# 04_InterfacePart.net
KiCad netlist of a schematic drawn in EasyEDA Pro
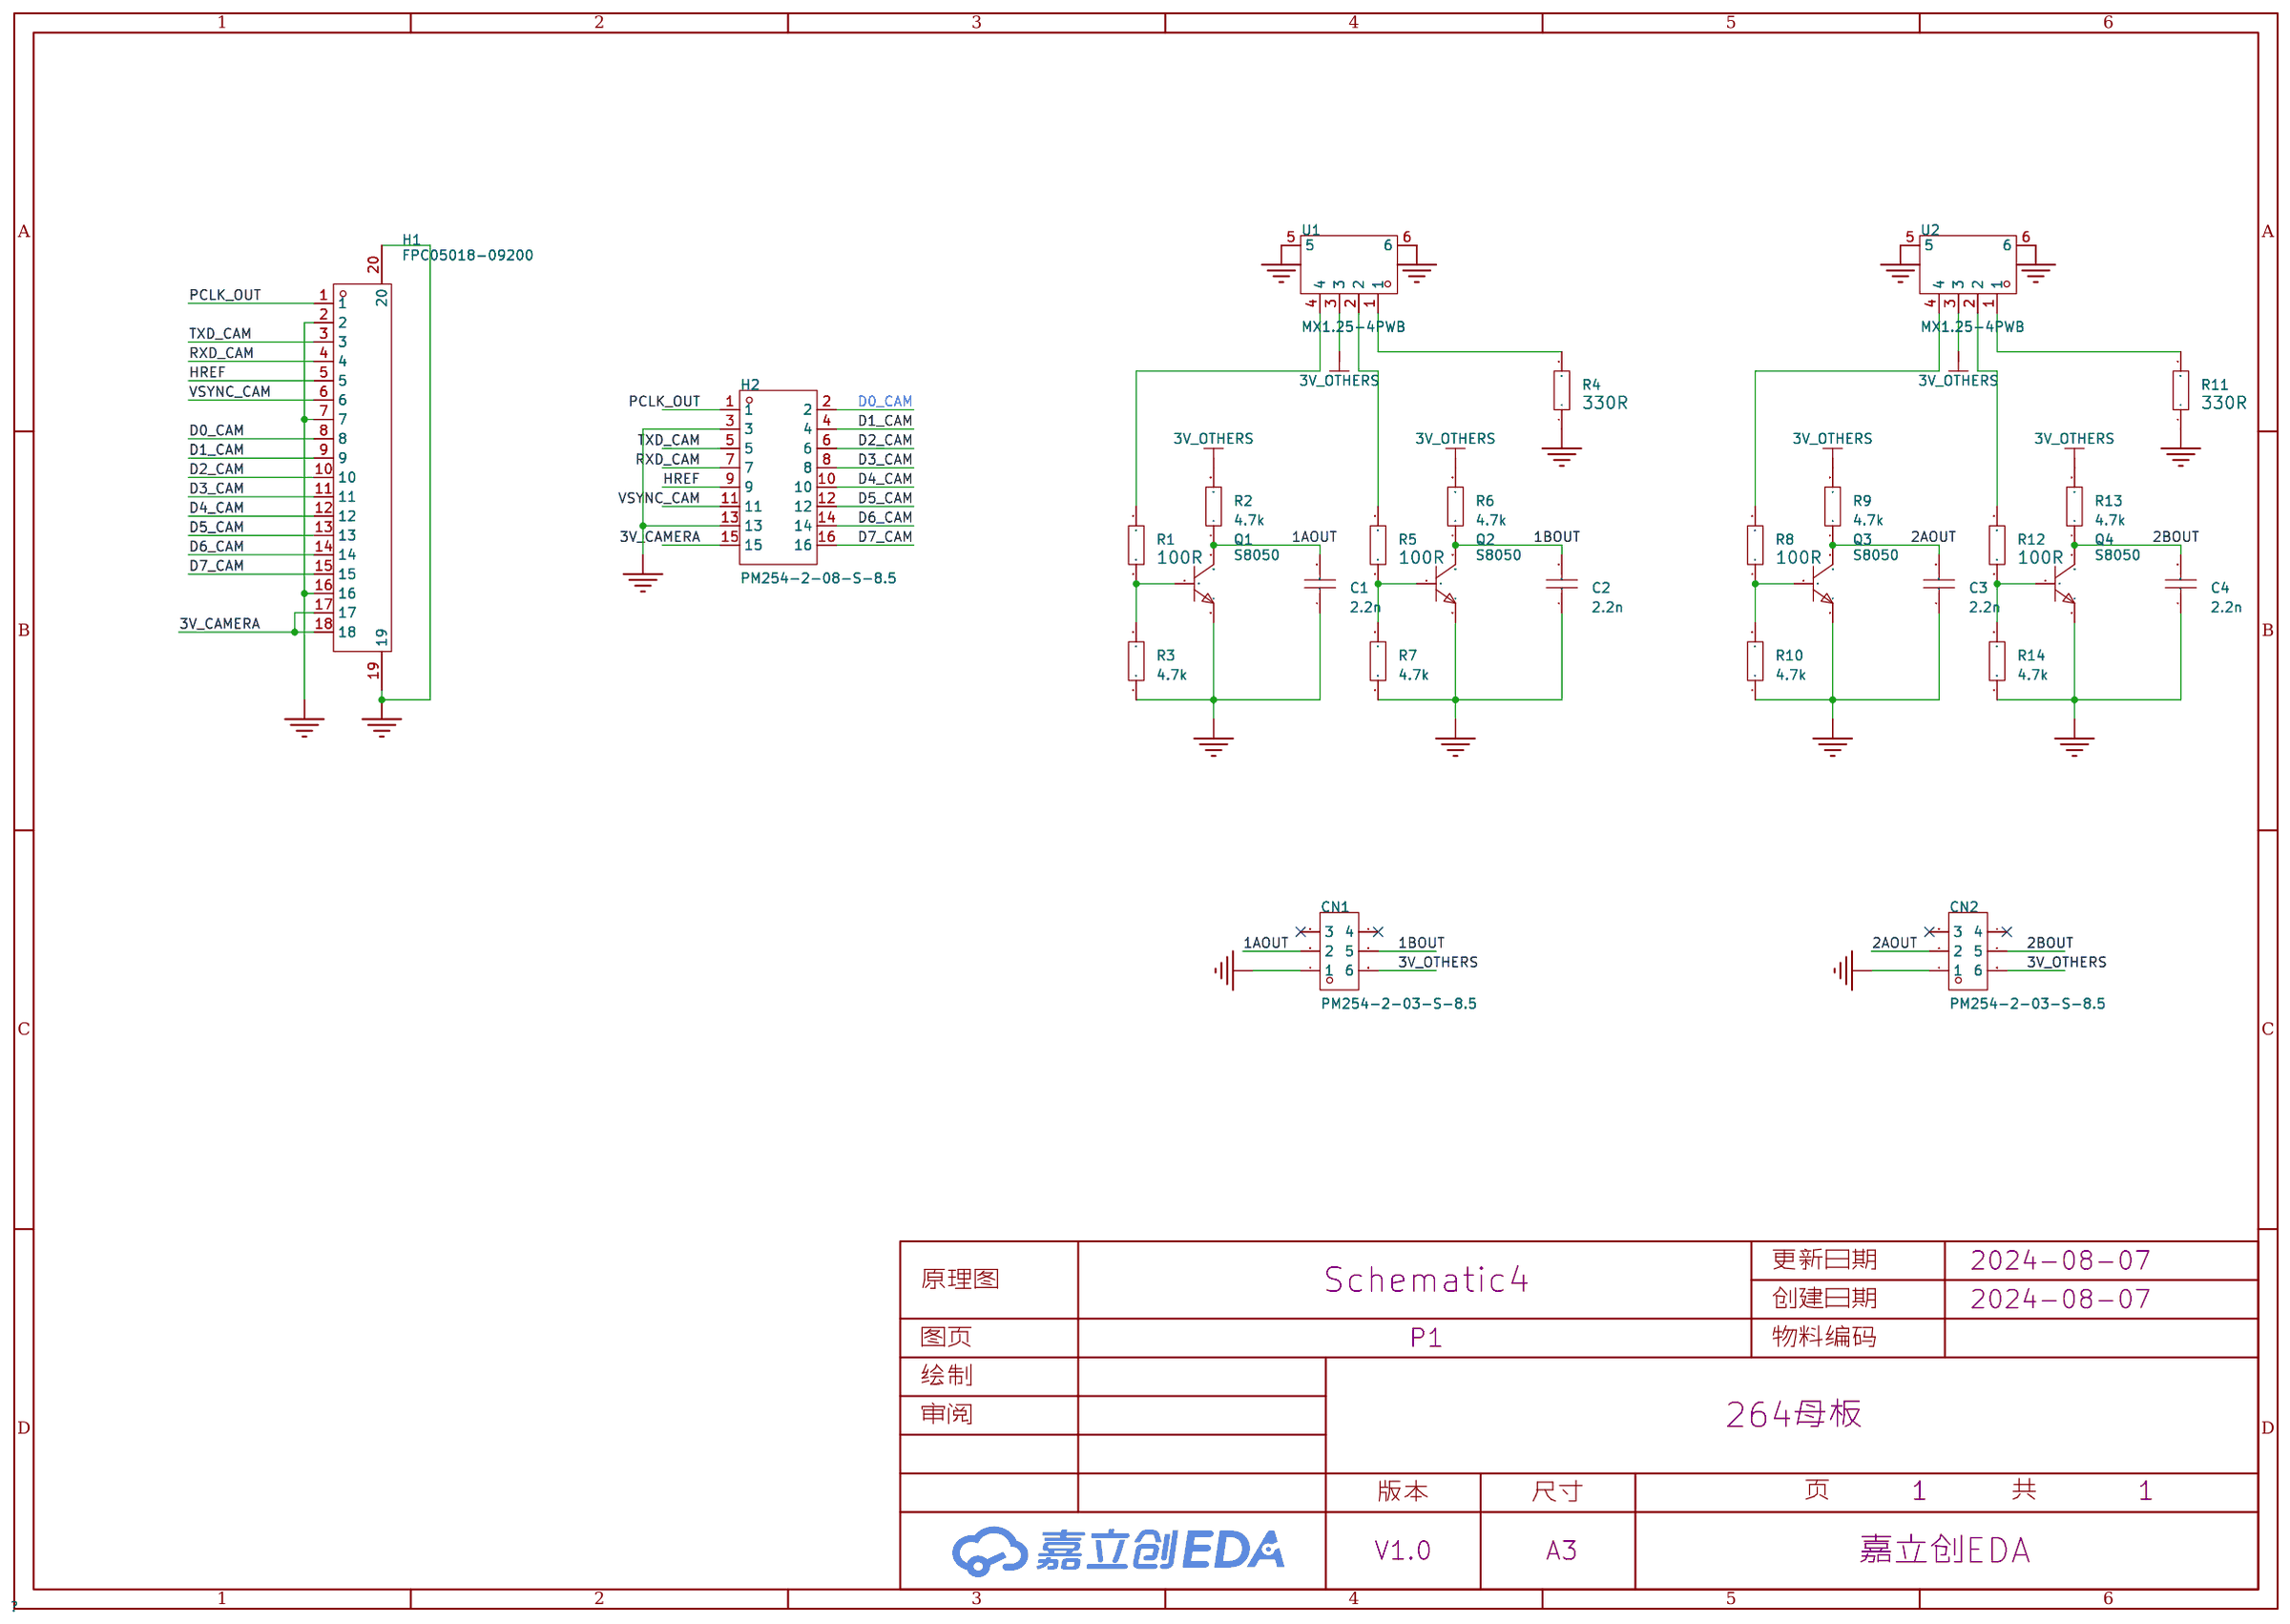
[diagram p0: schematic sheet]

(export (version "E")
  (design (tool "Eeschema 10.0.6"))
  (components
    (comp (ref "C1")
      (value "2.2n")
      (footprint "easyedapro:C0805")
      (libsource (lib "easyedapro") (part "电容-0805C"))
    )
    (comp (ref "C2")
      (value "2.2n")
      (footprint "easyedapro:C0805")
      (libsource (lib "easyedapro") (part "电容-0805C"))
    )
    (comp (ref "C3")
      (value "2.2n")
      (footprint "easyedapro:C0805")
      (libsource (lib "easyedapro") (part "电容-0805C"))
    )
    (comp (ref "C4")
      (value "2.2n")
      (footprint "easyedapro:C0805")
      (libsource (lib "easyedapro") (part "电容-0805C"))
    )
    (comp (ref "CN1")
      (value "PM254-2-03-S-8.5")
      (footprint "easyedapro:HDR-SMD_6P-P2.54-V-F-R2-C3-LS7.0")
      (fields (field (name "Manufacturer") "HCTL(华灿天禄)"))
      (libsource (lib "easyedapro") (part "PM254-2-03-S-8.5"))
    )
    (comp (ref "CN2")
      (value "PM254-2-03-S-8.5")
      (footprint "easyedapro:HDR-SMD_6P-P2.54-V-F-R2-C3-LS7.0")
      (fields (field (name "Manufacturer") "HCTL(华灿天禄)"))
      (libsource (lib "easyedapro") (part "PM254-2-03-S-8.5"))
    )
    (comp (ref "H1")
      (value "FPC05018-09200")
      (footprint "easyedapro:FPC-SMD_FPC05018-09200")
      (description "锁定特性:翻盖式;触点类型:下接;触点数量:18P;间距:0.5mm;安装类型:卧贴;工作温度范围:-25°C~+85°C;")
      (fields (field (name "Manufacturer") "ATOM(爱特姆)"))
      (libsource (lib "easyedapro") (part "FPC05018-09200"))
    )
    (comp (ref "H2")
      (value "PM254-2-08-S-8.5")
      (footprint "easyedapro:HDR-SMD_16P-P2.54-V-F-R2-C8-LS7.1")
      (fields (field (name "Manufacturer") "HCTL(华灿天禄)"))
      (libsource (lib "easyedapro") (part "PM254-2-08-S-8.5"))
    )
    (comp (ref "Q1")
      (value "S8050")
      (footprint "easyedapro:SOT-23-3_L2.9-W1.6-P1.90-LS2.8-BR")
      (fields (field (name "Manufacturer") "ElecSuper(静芯微）"))
      (libsource (lib "easyedapro") (part "S8050_C5249674"))
    )
    (comp (ref "Q2")
      (value "S8050")
      (footprint "easyedapro:SOT-23-3_L2.9-W1.6-P1.90-LS2.8-BR")
      (fields (field (name "Manufacturer") "ElecSuper(静芯微）"))
      (libsource (lib "easyedapro") (part "S8050_C5249674"))
    )
    (comp (ref "Q3")
      (value "S8050")
      (footprint "easyedapro:SOT-23-3_L2.9-W1.6-P1.90-LS2.8-BR")
      (fields (field (name "Manufacturer") "ElecSuper(静芯微）"))
      (libsource (lib "easyedapro") (part "S8050_C5249674"))
    )
    (comp (ref "Q4")
      (value "S8050")
      (footprint "easyedapro:SOT-23-3_L2.9-W1.6-P1.90-LS2.8-BR")
      (fields (field (name "Manufacturer") "ElecSuper(静芯微）"))
      (libsource (lib "easyedapro") (part "S8050_C5249674"))
    )
    (comp (ref "R1")
      (value "100R")
      (footprint "easyedapro:R0805")
      (description "电阻类型:厚膜电阻;阻值:1kΩ;精度:±1%;功率:125mW;温度系数:±100ppm/°C;最大工作电压:150V;工作温度范围:-55°C~+155°C;")
      (libsource (lib "easyedapro") (part "电阻_0805"))
    )
    (comp (ref "R2")
      (value "4.7k")
      (footprint "easyedapro:R0805")
      (description "电阻类型:厚膜电阻;阻值:1kΩ;精度:±1%;功率:125mW;温度系数:±100ppm/°C;最大工作电压:150V;工作温度范围:-55°C~+155°C;")
      (libsource (lib "easyedapro") (part "电阻_0805"))
    )
    (comp (ref "R3")
      (value "4.7k")
      (footprint "easyedapro:R0805")
      (description "电阻类型:厚膜电阻;阻值:1kΩ;精度:±1%;功率:125mW;温度系数:±100ppm/°C;最大工作电压:150V;工作温度范围:-55°C~+155°C;")
      (libsource (lib "easyedapro") (part "电阻_0805"))
    )
    (comp (ref "R4")
      (value "330R")
      (footprint "easyedapro:R0805")
      (description "电阻类型:厚膜电阻;阻值:1kΩ;精度:±1%;功率:125mW;温度系数:±100ppm/°C;最大工作电压:150V;工作温度范围:-55°C~+155°C;")
      (libsource (lib "easyedapro") (part "电阻_0805"))
    )
    (comp (ref "R5")
      (value "100R")
      (footprint "easyedapro:R0805")
      (description "电阻类型:厚膜电阻;阻值:1kΩ;精度:±1%;功率:125mW;温度系数:±100ppm/°C;最大工作电压:150V;工作温度范围:-55°C~+155°C;")
      (libsource (lib "easyedapro") (part "电阻_0805"))
    )
    (comp (ref "R6")
      (value "4.7k")
      (footprint "easyedapro:R0805")
      (description "电阻类型:厚膜电阻;阻值:1kΩ;精度:±1%;功率:125mW;温度系数:±100ppm/°C;最大工作电压:150V;工作温度范围:-55°C~+155°C;")
      (libsource (lib "easyedapro") (part "电阻_0805"))
    )
    (comp (ref "R7")
      (value "4.7k")
      (footprint "easyedapro:R0805")
      (description "电阻类型:厚膜电阻;阻值:1kΩ;精度:±1%;功率:125mW;温度系数:±100ppm/°C;最大工作电压:150V;工作温度范围:-55°C~+155°C;")
      (libsource (lib "easyedapro") (part "电阻_0805"))
    )
    (comp (ref "R8")
      (value "100R")
      (footprint "easyedapro:R0805")
      (description "电阻类型:厚膜电阻;阻值:1kΩ;精度:±1%;功率:125mW;温度系数:±100ppm/°C;最大工作电压:150V;工作温度范围:-55°C~+155°C;")
      (libsource (lib "easyedapro") (part "电阻_0805"))
    )
    (comp (ref "R9")
      (value "4.7k")
      (footprint "easyedapro:R0805")
      (description "电阻类型:厚膜电阻;阻值:1kΩ;精度:±1%;功率:125mW;温度系数:±100ppm/°C;最大工作电压:150V;工作温度范围:-55°C~+155°C;")
      (libsource (lib "easyedapro") (part "电阻_0805"))
    )
    (comp (ref "R10")
      (value "4.7k")
      (footprint "easyedapro:R0805")
      (description "电阻类型:厚膜电阻;阻值:1kΩ;精度:±1%;功率:125mW;温度系数:±100ppm/°C;最大工作电压:150V;工作温度范围:-55°C~+155°C;")
      (libsource (lib "easyedapro") (part "电阻_0805"))
    )
    (comp (ref "R11")
      (value "330R")
      (footprint "easyedapro:R0805")
      (description "电阻类型:厚膜电阻;阻值:1kΩ;精度:±1%;功率:125mW;温度系数:±100ppm/°C;最大工作电压:150V;工作温度范围:-55°C~+155°C;")
      (libsource (lib "easyedapro") (part "电阻_0805"))
    )
    (comp (ref "R12")
      (value "100R")
      (footprint "easyedapro:R0805")
      (description "电阻类型:厚膜电阻;阻值:1kΩ;精度:±1%;功率:125mW;温度系数:±100ppm/°C;最大工作电压:150V;工作温度范围:-55°C~+155°C;")
      (libsource (lib "easyedapro") (part "电阻_0805"))
    )
    (comp (ref "R13")
      (value "4.7k")
      (footprint "easyedapro:R0805")
      (description "电阻类型:厚膜电阻;阻值:1kΩ;精度:±1%;功率:125mW;温度系数:±100ppm/°C;最大工作电压:150V;工作温度范围:-55°C~+155°C;")
      (libsource (lib "easyedapro") (part "电阻_0805"))
    )
    (comp (ref "R14")
      (value "4.7k")
      (footprint "easyedapro:R0805")
      (description "电阻类型:厚膜电阻;阻值:1kΩ;精度:±1%;功率:125mW;温度系数:±100ppm/°C;最大工作电压:150V;工作温度范围:-55°C~+155°C;")
      (libsource (lib "easyedapro") (part "电阻_0805"))
    )
    (comp (ref "U1")
      (value "MX1.25-4PWB")
      (footprint "easyedapro:CONN-SMD_4P-P1.25_WAFER-MX1.25-4PWB")
      (description "插针结构:1x4P;间距:1.25mm;安装方式:卧贴;总PIN数:4P;排数:1;每排PIN数:4;额定电流:1A;工作温度范围:-25°C~+85°C;")
      (fields
        (field (name "Manufacturer Part") "WAFER-MX1.25-4PWB")
        (field (name "Manufacturer") "XUNPU(讯普)")
      )
      (libsource (lib "easyedapro") (part "WAFER-MX1.25-4PWB"))
    )
    (comp (ref "U2")
      (value "MX1.25-4PWB")
      (footprint "easyedapro:CONN-SMD_4P-P1.25_WAFER-MX1.25-4PWB")
      (description "插针结构:1x4P;间距:1.25mm;安装方式:卧贴;总PIN数:4P;排数:1;每排PIN数:4;额定电流:1A;工作温度范围:-25°C~+85°C;")
      (fields
        (field (name "Manufacturer Part") "WAFER-MX1.25-4PWB")
        (field (name "Manufacturer") "XUNPU(讯普)")
      )
      (libsource (lib "easyedapro") (part "WAFER-MX1.25-4PWB"))
    )
  )
  (nets
    (net (code "1") (name "/1AOUT") (class "Default")
      (node (ref "C1") (pin "2") (pinfunction "2_2") (pintype "input"))
      (node (ref "CN1") (pin "2") (pinfunction "2_2") (pintype "unspecified"))
      (node (ref "Q1") (pin "3") (pinfunction "C_3") (pintype "input"))
      (node (ref "R2") (pin "1") (pinfunction "1_1") (pintype "input"))
    )
    (net (code "2") (name "/1BOUT") (class "Default")
      (node (ref "C2") (pin "2") (pinfunction "2_2") (pintype "input"))
      (node (ref "CN1") (pin "5") (pinfunction "5_5") (pintype "unspecified"))
      (node (ref "Q2") (pin "3") (pinfunction "C_3") (pintype "input"))
      (node (ref "R6") (pin "1") (pinfunction "1_1") (pintype "input"))
    )
    (net (code "3") (name "/2AOUT") (class "Default")
      (node (ref "C3") (pin "2") (pinfunction "2_2") (pintype "input"))
      (node (ref "CN2") (pin "2") (pinfunction "2_2") (pintype "unspecified"))
      (node (ref "Q3") (pin "3") (pinfunction "C_3") (pintype "input"))
      (node (ref "R9") (pin "1") (pinfunction "1_1") (pintype "input"))
    )
    (net (code "4") (name "/2BOUT") (class "Default")
      (node (ref "C4") (pin "2") (pinfunction "2_2") (pintype "input"))
      (node (ref "CN2") (pin "5") (pinfunction "5_5") (pintype "unspecified"))
      (node (ref "Q4") (pin "3") (pinfunction "C_3") (pintype "input"))
      (node (ref "R13") (pin "1") (pinfunction "1_1") (pintype "input"))
    )
    (net (code "5") (name "/3V_CAMERA") (class "Default")
      (node (ref "H1") (pin "17") (pinfunction "17_17") (pintype "unspecified"))
      (node (ref "H1") (pin "18") (pinfunction "18_18") (pintype "unspecified"))
      (node (ref "H2") (pin "15") (pinfunction "15_15") (pintype "unspecified"))
    )
    (net (code "6") (name "/D0_CAM") (class "Default")
      (node (ref "H1") (pin "8") (pinfunction "8_8") (pintype "unspecified"))
      (node (ref "H2") (pin "2") (pinfunction "2_2") (pintype "unspecified"))
    )
    (net (code "7") (name "/D1_CAM") (class "Default")
      (node (ref "H1") (pin "9") (pinfunction "9_9") (pintype "unspecified"))
      (node (ref "H2") (pin "4") (pinfunction "4_4") (pintype "unspecified"))
    )
    (net (code "8") (name "/D2_CAM") (class "Default")
      (node (ref "H1") (pin "10") (pinfunction "10_10") (pintype "unspecified"))
      (node (ref "H2") (pin "6") (pinfunction "6_6") (pintype "unspecified"))
    )
    (net (code "9") (name "/D3_CAM") (class "Default")
      (node (ref "H1") (pin "11") (pinfunction "11_11") (pintype "unspecified"))
      (node (ref "H2") (pin "8") (pinfunction "8_8") (pintype "unspecified"))
    )
    (net (code "10") (name "/D4_CAM") (class "Default")
      (node (ref "H1") (pin "12") (pinfunction "12_12") (pintype "unspecified"))
      (node (ref "H2") (pin "10") (pinfunction "10_10") (pintype "unspecified"))
    )
    (net (code "11") (name "/D5_CAM") (class "Default")
      (node (ref "H1") (pin "13") (pinfunction "13_13") (pintype "unspecified"))
      (node (ref "H2") (pin "12") (pinfunction "12_12") (pintype "unspecified"))
    )
    (net (code "12") (name "/D6_CAM") (class "Default")
      (node (ref "H1") (pin "14") (pinfunction "14_14") (pintype "unspecified"))
      (node (ref "H2") (pin "14") (pinfunction "14_14") (pintype "unspecified"))
    )
    (net (code "13") (name "/D7_CAM") (class "Default")
      (node (ref "H1") (pin "15") (pinfunction "15_15") (pintype "unspecified"))
      (node (ref "H2") (pin "16") (pinfunction "16_16") (pintype "unspecified"))
    )
    (net (code "14") (name "/HREF") (class "Default")
      (node (ref "H1") (pin "5") (pinfunction "5_5") (pintype "unspecified"))
      (node (ref "H2") (pin "9") (pinfunction "9_9") (pintype "unspecified"))
    )
    (net (code "15") (name "/PCLK_OUT") (class "Default")
      (node (ref "H1") (pin "1") (pinfunction "1_1") (pintype "unspecified"))
      (node (ref "H2") (pin "1") (pinfunction "1_1") (pintype "unspecified"))
    )
    (net (code "16") (name "/RXD_CAM") (class "Default")
      (node (ref "H1") (pin "4") (pinfunction "4_4") (pintype "unspecified"))
      (node (ref "H2") (pin "7") (pinfunction "7_7") (pintype "unspecified"))
    )
    (net (code "17") (name "/TXD_CAM") (class "Default")
      (node (ref "H1") (pin "3") (pinfunction "3_3") (pintype "unspecified"))
      (node (ref "H2") (pin "5") (pinfunction "5_5") (pintype "unspecified"))
    )
    (net (code "18") (name "/VSYNC_CAM") (class "Default")
      (node (ref "H1") (pin "6") (pinfunction "6_6") (pintype "unspecified"))
      (node (ref "H2") (pin "11") (pinfunction "11_11") (pintype "unspecified"))
    )
    (net (code "19") (name "3V_OTHERS") (class "Default")
      (node (ref "CN1") (pin "6") (pinfunction "6_6") (pintype "unspecified"))
      (node (ref "CN2") (pin "6") (pinfunction "6_6") (pintype "unspecified"))
      (node (ref "R13") (pin "2") (pinfunction "2_2") (pintype "input"))
      (node (ref "R2") (pin "2") (pinfunction "2_2") (pintype "input"))
      (node (ref "R6") (pin "2") (pinfunction "2_2") (pintype "input"))
      (node (ref "R9") (pin "2") (pinfunction "2_2") (pintype "input"))
      (node (ref "U1") (pin "3") (pinfunction "3_3") (pintype "unspecified"))
      (node (ref "U2") (pin "3") (pinfunction "3_3") (pintype "unspecified"))
    )
    (net (code "20") (name "GND") (class "Default")
      (node (ref "C1") (pin "1") (pinfunction "1_1") (pintype "input"))
      (node (ref "C2") (pin "1") (pinfunction "1_1") (pintype "input"))
      (node (ref "C3") (pin "1") (pinfunction "1_1") (pintype "input"))
      (node (ref "C4") (pin "1") (pinfunction "1_1") (pintype "input"))
      (node (ref "CN1") (pin "1") (pinfunction "1_1") (pintype "unspecified"))
      (node (ref "CN2") (pin "1") (pinfunction "1_1") (pintype "unspecified"))
      (node (ref "H1") (pin "16") (pinfunction "16_16") (pintype "unspecified"))
      (node (ref "H1") (pin "19") (pinfunction "19_19") (pintype "unspecified"))
      (node (ref "H1") (pin "2") (pinfunction "2_2") (pintype "unspecified"))
      (node (ref "H1") (pin "20") (pinfunction "20_20") (pintype "unspecified"))
      (node (ref "H1") (pin "7") (pinfunction "7_7") (pintype "unspecified"))
      (node (ref "H2") (pin "13") (pinfunction "13_13") (pintype "unspecified"))
      (node (ref "H2") (pin "3") (pinfunction "3_3") (pintype "unspecified"))
      (node (ref "Q1") (pin "2") (pinfunction "E_2") (pintype "input"))
      (node (ref "Q2") (pin "2") (pinfunction "E_2") (pintype "input"))
      (node (ref "Q3") (pin "2") (pinfunction "E_2") (pintype "input"))
      (node (ref "Q4") (pin "2") (pinfunction "E_2") (pintype "input"))
      (node (ref "R10") (pin "1") (pinfunction "1_1") (pintype "input"))
      (node (ref "R11") (pin "1") (pinfunction "1_1") (pintype "input"))
      (node (ref "R14") (pin "1") (pinfunction "1_1") (pintype "input"))
      (node (ref "R3") (pin "1") (pinfunction "1_1") (pintype "input"))
      (node (ref "R4") (pin "1") (pinfunction "1_1") (pintype "input"))
      (node (ref "R7") (pin "1") (pinfunction "1_1") (pintype "input"))
      (node (ref "U1") (pin "5") (pinfunction "5_5") (pintype "unspecified"))
      (node (ref "U1") (pin "6") (pinfunction "6_6") (pintype "unspecified"))
      (node (ref "U2") (pin "5") (pinfunction "5_5") (pintype "unspecified"))
      (node (ref "U2") (pin "6") (pinfunction "6_6") (pintype "unspecified"))
    )
    (net (code "21") (name "Net-(Q1-B)") (class "Default")
      (node (ref "Q1") (pin "1") (pinfunction "B_1") (pintype "input"))
      (node (ref "R1") (pin "1") (pinfunction "1_1") (pintype "input"))
      (node (ref "R3") (pin "2") (pinfunction "2_2") (pintype "input"))
    )
    (net (code "22") (name "Net-(Q2-B)") (class "Default")
      (node (ref "Q2") (pin "1") (pinfunction "B_1") (pintype "input"))
      (node (ref "R5") (pin "1") (pinfunction "1_1") (pintype "input"))
      (node (ref "R7") (pin "2") (pinfunction "2_2") (pintype "input"))
    )
    (net (code "23") (name "Net-(Q3-B)") (class "Default")
      (node (ref "Q3") (pin "1") (pinfunction "B_1") (pintype "input"))
      (node (ref "R10") (pin "2") (pinfunction "2_2") (pintype "input"))
      (node (ref "R8") (pin "1") (pinfunction "1_1") (pintype "input"))
    )
    (net (code "24") (name "Net-(Q4-B)") (class "Default")
      (node (ref "Q4") (pin "1") (pinfunction "B_1") (pintype "input"))
      (node (ref "R12") (pin "1") (pinfunction "1_1") (pintype "input"))
      (node (ref "R14") (pin "2") (pinfunction "2_2") (pintype "input"))
    )
    (net (code "25") (name "Net-(R1-Pad2)") (class "Default")
      (node (ref "R1") (pin "2") (pinfunction "2_2") (pintype "input"))
      (node (ref "U1") (pin "4") (pinfunction "4_4") (pintype "unspecified"))
    )
    (net (code "26") (name "Net-(R4-Pad2)") (class "Default")
      (node (ref "R4") (pin "2") (pinfunction "2_2") (pintype "input"))
      (node (ref "U1") (pin "1") (pinfunction "1_1") (pintype "unspecified"))
    )
    (net (code "27") (name "Net-(R5-Pad2)") (class "Default")
      (node (ref "R5") (pin "2") (pinfunction "2_2") (pintype "input"))
      (node (ref "U1") (pin "2") (pinfunction "2_2") (pintype "unspecified"))
    )
    (net (code "28") (name "Net-(R8-Pad2)") (class "Default")
      (node (ref "R8") (pin "2") (pinfunction "2_2") (pintype "input"))
      (node (ref "U2") (pin "4") (pinfunction "4_4") (pintype "unspecified"))
    )
    (net (code "29") (name "Net-(R11-Pad2)") (class "Default")
      (node (ref "R11") (pin "2") (pinfunction "2_2") (pintype "input"))
      (node (ref "U2") (pin "1") (pinfunction "1_1") (pintype "unspecified"))
    )
    (net (code "30") (name "Net-(R12-Pad2)") (class "Default")
      (node (ref "R12") (pin "2") (pinfunction "2_2") (pintype "input"))
      (node (ref "U2") (pin "2") (pinfunction "2_2") (pintype "unspecified"))
    )
    (net (code "31") (name "unconnected-(CN1-Pad3)") (class "Default")
      (node (ref "CN1") (pin "3") (pinfunction "3_3") (pintype "unspecified+no_connect"))
    )
    (net (code "32") (name "unconnected-(CN1-Pad4)") (class "Default")
      (node (ref "CN1") (pin "4") (pinfunction "4_4") (pintype "unspecified+no_connect"))
    )
    (net (code "33") (name "unconnected-(CN2-Pad3)") (class "Default")
      (node (ref "CN2") (pin "3") (pinfunction "3_3") (pintype "unspecified+no_connect"))
    )
    (net (code "34") (name "unconnected-(CN2-Pad4)") (class "Default")
      (node (ref "CN2") (pin "4") (pinfunction "4_4") (pintype "unspecified+no_connect"))
    )
  )
)
